# Power_Distribution.net
KiCad netlist of a schematic drawn in Altium Designer
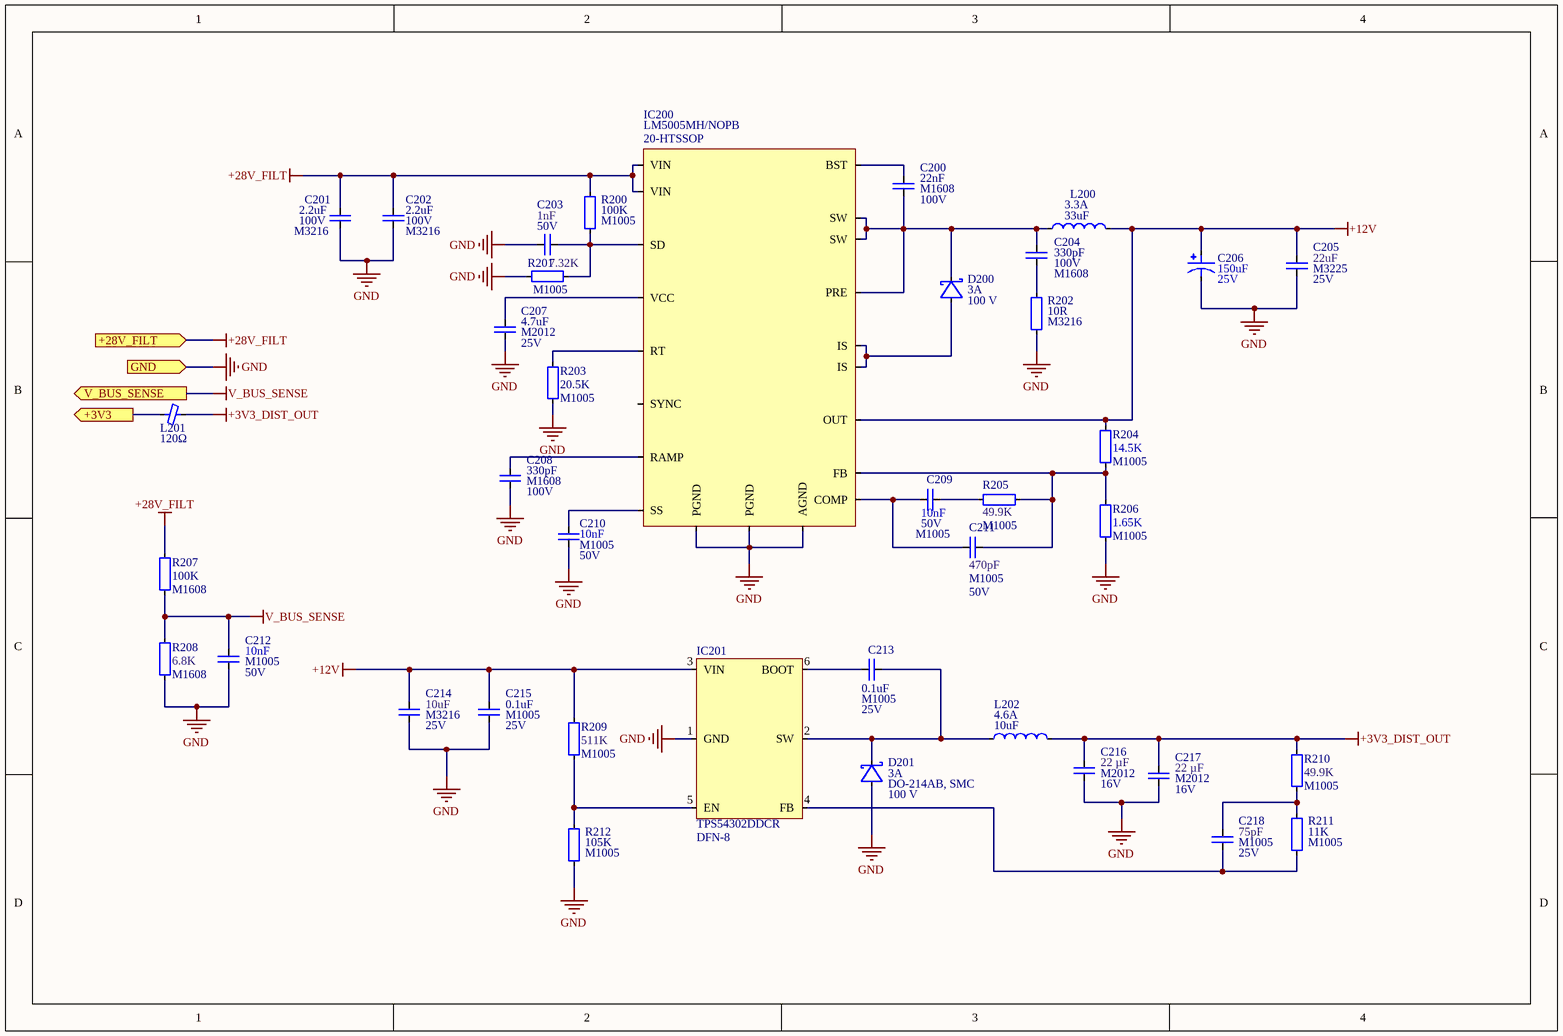
[diagram p0: Power_Distribution.SchDoc]

(export (version "E")
  (design (tool "Eeschema 10.0.6"))
  (components
    (comp (ref "C200")
      (value "22nF")
      (footprint "Capacitor_Seramic_M1608_I0603")
      (description "Cap, Cer, 22nF, 100V, M1608")
      (fields
        (field (name "TOLERANCE") "±10%")
        (field (name "MANUFACTURER PART NUMBER") "CC0603KRX7R0BB223")
        (field (name "PACKAGE") "M1608")
        (field (name "RATED VOLTAGE") "100V")
      )
      (libsource (lib "Capacitor") (part "Capacitor_Seramic"))
    )
    (comp (ref "C201")
      (value "2.2uF")
      (footprint "Capacitor_Seramic_M2012_I0805")
      (description "Cap, Cer, 2.2uF, 100V, M3216")
      (fields
        (field (name "TOLERANCE") "±10%")
        (field (name "MANUFACTURER PART NUMBER") "AC1206KKX7R0BB225")
        (field (name "PACKAGE") "M3216")
        (field (name "RATED VOLTAGE") "100V")
      )
      (libsource (lib "Capacitor") (part "Capacitor_Seramic"))
    )
    (comp (ref "C202")
      (value "2.2uF")
      (footprint "Capacitor_Seramic_M2012_I0805")
      (description "Cap, Cer, 2.2uF, 100V, M3216")
      (fields
        (field (name "TOLERANCE") "±10%")
        (field (name "MANUFACTURER PART NUMBER") "AC1206KKX7R0BB225")
        (field (name "PACKAGE") "M3216")
        (field (name "RATED VOLTAGE") "100V")
      )
      (libsource (lib "Capacitor") (part "Capacitor_Seramic"))
    )
    (comp (ref "C203")
      (value "1nF")
      (footprint "Capacitor_Seramic_M1005_I0402")
      (description "Cap, Cer, 1nF, 50V, M1005")
      (fields
        (field (name "TOLERANCE") "±10%")
        (field (name "MANUFACTURER PART NUMBER") "CC0402KRX7R9BB102")
        (field (name "RATED VOLTAGE") "50V")
        (field (name "COMPONENTLINK1URL") "C:\\Users\\User\\OneDrive - Karadeniz Teknik University\\Masaüstü\\pcb\\Altium-Designer-ile-Elektronik-Devre-Karti-Tasarimi_2024-main\\Datasheets\\Capacitor\\Walsin - Multilayer Ceramic Capacitors.pdf")
      )
      (libsource (lib "Capacitor") (part "Capacitor_Seramic"))
    )
    (comp (ref "C204")
      (value "330pF")
      (footprint "Capacitor_Seramic_M1608_I0603")
      (description "Cap, Cer, 330pF, 100V, M1608")
      (fields
        (field (name "TOLERANCE") "±5%")
        (field (name "MANUFACTURER PART NUMBER") "CC0603JRNPO0BN331")
        (field (name "PACKAGE") "M1608")
        (field (name "RATED VOLTAGE") "100V")
      )
      (libsource (lib "Capacitor") (part "Capacitor_Seramic"))
    )
    (comp (ref "C205")
      (value "22uF")
      (footprint "Capacitor_Seramic_M3225_I1210")
      (description "Cap, Cer, 22uF, 25V, M3225")
      (fields
        (field (name "TOLERANCE") "±10%")
        (field (name "MANUFACTURER PART NUMBER") "GRM32ER71E226KE15L")
        (field (name "PACKAGE") "M3225")
        (field (name "RATED VOLTAGE") "25V")
        (field (name "COMPONENTLINK1URL") "C:\\Users\\User\\OneDrive - Karadeniz Teknik University\\Masaüstü\\pcb\\Altium-Designer-ile-Elektronik-Devre-Karti-Tasarimi_2024-main\\Datasheets\\Capacitor\\Murata - Multilayer Ceramic Capacitors.pdf")
      )
      (libsource (lib "Capacitor") (part "Capacitor_Seramic"))
    )
    (comp (ref "C206")
      (value "150uF")
      (footprint "CAP_ZK_D8_PAN")
      (description "Cap, Aluminum")
      (fields
        (field (name "TOLERANCE") "±20%")
        (field (name "MANUFACTURER") "Panasonic")
        (field (name "RATED VOLTAGE") "25V")
      )
      (libsource (lib "Capacitor") (part "Capacitor_Aluminum"))
    )
    (comp (ref "C207")
      (value "4.7uF")
      (footprint "Capacitor_Seramic_M2012_I0805")
      (description "Cap, Cer, 4.7uF, 25V, M2012")
      (fields
        (field (name "TOLERANCE") "±10%")
        (field (name "MANUFACTURER PART NUMBER") "C2012X7R1E475K125AB")
        (field (name "PACKAGE") "M2012")
        (field (name "RATED VOLTAGE") "25V")
      )
      (libsource (lib "Capacitor") (part "Capacitor_Seramic"))
    )
    (comp (ref "C208")
      (value "330pF")
      (footprint "Capacitor_Seramic_M1608_I0603")
      (description "Cap, Cer, 330pF, 100V, M1608")
      (fields
        (field (name "TOLERANCE") "±5%")
        (field (name "MANUFACTURER PART NUMBER") "CC0603JRNPO0BN331")
        (field (name "PACKAGE") "M1608")
        (field (name "RATED VOLTAGE") "100V")
      )
      (libsource (lib "Capacitor") (part "Capacitor_Seramic"))
    )
    (comp (ref "C209")
      (value "10nF")
      (footprint "Capacitor_Seramic_M1005_I0402")
      (description "Cap, Cer, 10nF, 50V, M1005")
      (fields
        (field (name "TOLERANCE") "±10%")
        (field (name "MANUFACTURER PART NUMBER") "CC0402KRX7R9BB103")
        (field (name "PACKAGE") "M1005")
        (field (name "RATED VOLTAGE") "50V")
      )
      (libsource (lib "Capacitor") (part "Capacitor_Seramic"))
    )
    (comp (ref "C210")
      (value "10nF")
      (footprint "Capacitor_Seramic_M1005_I0402")
      (description "Cap, Cer, 10nF, 50V, M1005")
      (fields
        (field (name "TOLERANCE") "±10%")
        (field (name "MANUFACTURER PART NUMBER") "CC0402KRX7R9BB103")
        (field (name "PACKAGE") "M1005")
        (field (name "RATED VOLTAGE") "50V")
      )
      (libsource (lib "Capacitor") (part "Capacitor_Seramic"))
    )
    (comp (ref "C211")
      (value "470pF")
      (footprint "Capacitor_Seramic_M1005_I0402")
      (description "Cap, Cer, 470pF, 50V, M1005")
      (fields
        (field (name "TOLERANCE") "±5%")
        (field (name "MANUFACTURER PART NUMBER") "CC0402JRNPO9BN471")
        (field (name "PACKAGE") "M1005")
        (field (name "RATED VOLTAGE") "50V")
        (field (name "COMPONENTLINK1URL") "C:\\Users\\User\\OneDrive - Karadeniz Teknik University\\Masaüstü\\pcb\\Altium-Designer-ile-Elektronik-Devre-Karti-Tasarimi_2024-main\\Datasheets\\Capacitor\\Walsin - Multilayer Ceramic Capacitors.pdf")
      )
      (libsource (lib "Capacitor") (part "Capacitor_Seramic"))
    )
    (comp (ref "C212")
      (value "10nF")
      (footprint "Capacitor_Seramic_M1005_I0402")
      (description "Cap, Cer, 10nF, 50V, M1005")
      (fields
        (field (name "TOLERANCE") "±10%")
        (field (name "MANUFACTURER PART NUMBER") "CC0402KRX7R9BB103")
        (field (name "PACKAGE") "M1005")
        (field (name "RATED VOLTAGE") "50V")
      )
      (libsource (lib "Capacitor") (part "Capacitor_Seramic"))
    )
    (comp (ref "C213")
      (value "0.1uF")
      (footprint "Capacitor_Seramic_M1005_I0402")
      (description "Cap, Cer, 0.1uF, 25V, M1005")
      (fields
        (field (name "TOLERANCE") "±10%")
        (field (name "MANUFACTURER PART NUMBER") "CC0402KRX7R8BB104")
        (field (name "PACKAGE") "M1005")
        (field (name "RATED VOLTAGE") "25V")
      )
      (libsource (lib "Capacitor") (part "Capacitor_Seramic"))
    )
    (comp (ref "C214")
      (value "10uF")
      (footprint "Capacitor_Seramic_M3216_I1206")
      (description "Cap, Cer, 10uF, 25V, M3216")
      (fields
        (field (name "TOLERANCE") "±10%")
        (field (name "MANUFACTURER PART NUMBER") "CL31B106KAHNFNE")
        (field (name "PACKAGE") "M3216")
        (field (name "RATED VOLTAGE") "25V")
        (field (name "COMPONENTLINK1URL") "C:\\Users\\User\\OneDrive - Karadeniz Teknik University\\Masaüstü\\pcb\\Altium-Designer-ile-Elektronik-Devre-Karti-Tasarimi_2024-main\\Datasheets\\Capacitor\\Walsin - Multilayer Ceramic Capacitors.pdf")
      )
      (libsource (lib "Capacitor") (part "Capacitor_Seramic"))
    )
    (comp (ref "C215")
      (value "0.1uF")
      (footprint "Capacitor_Seramic_M1005_I0402")
      (description "Cap, Cer, 0.1uF, 25V, M1005")
      (fields
        (field (name "TOLERANCE") "±10%")
        (field (name "MANUFACTURER PART NUMBER") "CC0402KRX7R8BB104")
        (field (name "PACKAGE") "M1005")
        (field (name "RATED VOLTAGE") "25V")
      )
      (libsource (lib "Capacitor") (part "Capacitor_Seramic"))
    )
    (comp (ref "C216")
      (value "22 µF")
      (footprint "Capacitor_Seramic_M2012_I0805")
      (description "Cap, Cer, 22uF, 16V, M2012")
      (fields
        (field (name "TOLERANCE") "20%")
        (field (name "MANUFACTURER PART NUMBER") "GRM21BR61C226ME44L")
        (field (name "PACKAGE") "M2012")
        (field (name "RATED VOLTAGE") "16V")
        (field (name "COMPONENTLINK1URL") "C:\\Users\\User\\OneDrive - Karadeniz Teknik University\\Masaüstü\\pcb\\Altium-Designer-ile-Elektronik-Devre-Karti-Tasarimi_2024-main\\Datasheets\\Capacitor\\Murata - Multilayer Ceramic Capacitors.pdf")
      )
      (libsource (lib "Capacitor") (part "Capacitor_Seramic"))
    )
    (comp (ref "C217")
      (value "22 µF")
      (footprint "Capacitor_Seramic_M2012_I0805")
      (description "Cap, Cer, 22uF, 16V, M2012")
      (fields
        (field (name "TOLERANCE") "20%")
        (field (name "MANUFACTURER PART NUMBER") "GRM21BR61C226ME44L")
        (field (name "PACKAGE") "M2012")
        (field (name "RATED VOLTAGE") "16V")
        (field (name "COMPONENTLINK1URL") "C:\\Users\\User\\OneDrive - Karadeniz Teknik University\\Masaüstü\\pcb\\Altium-Designer-ile-Elektronik-Devre-Karti-Tasarimi_2024-main\\Datasheets\\Capacitor\\Murata - Multilayer Ceramic Capacitors.pdf")
      )
      (libsource (lib "Capacitor") (part "Capacitor_Seramic"))
    )
    (comp (ref "C218")
      (value "75pF")
      (footprint "Capacitor_Seramic_M1005_I0402")
      (description "Cap, Cer, 75pF, 25V, M1005")
      (fields
        (field (name "TOLERANCE") "±5%")
        (field (name "MANUFACTURER PART NUMBER") "CC0402JRNPO9BN750")
        (field (name "PACKAGE") "M1005")
        (field (name "RATED VOLTAGE") "25V")
        (field (name "COMPONENTLINK1URL") "C:\\Users\\User\\OneDrive - Karadeniz Teknik University\\Masaüstü\\pcb\\Altium-Designer-ile-Elektronik-Devre-Karti-Tasarimi_2024-main\\Datasheets\\Capacitor\\Walsin - Multilayer Ceramic Capacitors.pdf")
      )
      (libsource (lib "Capacitor") (part "Capacitor_Seramic"))
    )
    (comp (ref "D200")
      (value "Diode_Schottky")
      (footprint "SMC_DIO")
      (fields
        (field (name "MANUFACTURER PART NUMBER") "B3100-13-F")
        (field (name "MANUFACTURER") "Diodes Incorporated")
        (field (name "CURRENT") "3A")
        (field (name "VOLTAGE") "100 V")
      )
      (libsource (lib "Diode") (part "Diode_Schottky"))
    )
    (comp (ref "D201")
      (value "Diode_Schottky")
      (footprint "SMC_DIO")
      (fields
        (field (name "MANUFACTURER PART NUMBER") "B3100-13-F")
        (field (name "MANUFACTURER") "Diodes Incorporated")
        (field (name "CURRENT") "3A")
        (field (name "PACKAGE") "DO-214AB, SMC")
        (field (name "VOLTAGE") "100 V")
      )
      (libsource (lib "Diode") (part "Diode_Schottky"))
    )
    (comp (ref "IC200")
      (value "TI, LM5005, 20-HTSSOP")
      (footprint "TI, LM5005, 20-HTSSOP")
      (description "IC, Power, DC-DC, Texas Instruments, LM5005, HTSSOP, 20 Pin")
      (fields
        (field (name "MANUFACTURER") "Texas Instruments")
        (field (name "MANUFACTURER PART NUMBER") "LM5005MH/NOPB")
        (field (name "PACKAGE") "20-HTSSOP")
        (field (name "COMPONENTLINK1URL") "C:\\Users\\User\\OneDrive - Karadeniz Teknik University\\Masaüstü\\pcb\\kütüphane\\Datasheet\\lm5005.pdf")
      )
      (libsource (lib "IC - Power - DC-DC") (part "TI, LM5005, 20-HTSSOP"))
    )
    (comp (ref "IC201")
      (value "TI, TPS54302")
      (footprint "SOT-23-6Pin")
      (description "IC, Power, DC-DC, Texas Instruments, TPS54302")
      (fields
        (field (name "MANUFACTURER") "Texas Instruments")
        (field (name "MANUFACTURER PART NUMBER") "TPS54302DDCR")
        (field (name "PACKAGE") "DFN-8")
        (field (name "COMPONENTLINK1URL") "C:\\Users\\User\\OneDrive - Karadeniz Teknik University\\Masaüstü\\pcb\\kütüphane\\Datasheet\\tps54302.pdf")
      )
      (libsource (lib "IC - Power - DC-DC") (part "TI, TPS54302"))
    )
    (comp (ref "L200")
      (value "33uF")
      (footprint "Bourns - SRR1280")
      (description "Inductor")
      (fields
        (field (name "MANUFACTURER PART NUMBER") "SRR1280-330M")
        (field (name "MANUFACTURER") "Bourns Inc.")
        (field (name "SATURATION CURRENT") "3.3A")
      )
      (libsource (lib "Inductor") (part "Inductor"))
    )
    (comp (ref "L201")
      (value "120Ω")
      (footprint "Ferrite_Bead_Smd_M1608_I0603")
      (fields
        (field (name "MANUFACTURER PART NUMBER") "BLM18PG121SN1D")
        (field (name "MANUFACTURER") "Murata Electronics")
        (field (name "Comment") "Ferrite Bead")
      )
      (libsource (lib "Inductor") (part "Ferrite Bead"))
    )
    (comp (ref "L202")
      (value "10uF")
      (footprint "Bourns - SRN6045TA")
      (description "Inductor")
      (fields
        (field (name "MANUFACTURER PART NUMBER") "SRN6045TA-100MCT-ND")
        (field (name "MANUFACTURER") "Bourns Inc.")
        (field (name "SATURATION CURRENT") "4.6A")
      )
      (libsource (lib "Inductor") (part "Inductor"))
    )
    (comp (ref "R200")
      (value "100K")
      (footprint "Resistor_SMD_M1005_I0402")
      (description "Res, 100K, 1%, M1005")
      (fields
        (field (name "MANUFACTURER") "Yageo")
        (field (name "MANUFACTURER PART NUMBER") "RC0402FR-07100KP")
        (field (name "PACKAGE") "M1005")
      )
      (libsource (lib "Resistor") (part "Resistor"))
    )
    (comp (ref "R201")
      (value "7.32K")
      (footprint "Resistor_SMD_M1005_I0402")
      (description "Res, 7.32K, 1%, M1005")
      (fields
        (field (name "MANUFACTURER") "YAGEO")
        (field (name "MANUFACTURER PART NUMBER") "RC0402FR-077K32L")
        (field (name "PACKAGE") "M1005")
      )
      (libsource (lib "Resistor") (part "Resistor"))
    )
    (comp (ref "R202")
      (value "10R")
      (footprint "Resistor_SMD_M3216_I1206")
      (fields
        (field (name "MANUFACTURER") "Yageo")
        (field (name "MANUFACTURER PART NUMBER") "RC1206FR-0710RL")
        (field (name "PACKAGE") "M3216")
        (field (name "Comment") "Resistor")
      )
      (libsource (lib "Resistor") (part "Resistor"))
    )
    (comp (ref "R203")
      (value "20.5K")
      (footprint "Resistor_SMD_M1005_I0402")
      (description "Res, 20.5K, 1%, M1005")
      (fields
        (field (name "MANUFACTURER") "YAGEO")
        (field (name "MANUFACTURER PART NUMBER") "RC0402FR-0720K5L")
        (field (name "PACKAGE") "M1005")
      )
      (libsource (lib "Resistor") (part "Resistor"))
    )
    (comp (ref "R204")
      (value "14.5K")
      (footprint "Resistor_SMD_M1005_I0402")
      (description "Res, 1.5K, 1%, M1005")
      (fields
        (field (name "MANUFACTURER") "Yageo")
        (field (name "MANUFACTURER PART NUMBER") "RC0402FR-071K5L")
        (field (name "PACKAGE") "M1005")
      )
      (libsource (lib "Resistor") (part "Resistor"))
    )
    (comp (ref "R205")
      (value "49.9K")
      (footprint "Resistor_SMD_M1005_I0402")
      (description "Res, 49.9K, 1%, M1005")
      (fields
        (field (name "MANUFACTURER") "YAGEO")
        (field (name "MANUFACTURER PART NUMBER") "RC0402FR-0749K9L")
        (field (name "PACKAGE") "M1005")
      )
      (libsource (lib "Resistor") (part "Resistor"))
    )
    (comp (ref "R206")
      (value "1.65K")
      (footprint "Resistor_SMD_M1005_I0402")
      (description "Res, 1.65K, 1%, M1005")
      (fields
        (field (name "MANUFACTURER") "YAGEO")
        (field (name "MANUFACTURER PART NUMBER") "RC0402FR-071K65L")
        (field (name "PACKAGE") "M1005")
      )
      (libsource (lib "Resistor") (part "Resistor"))
    )
    (comp (ref "R207")
      (value "100K")
      (footprint "Resistor_SMD_M1608_I0603")
      (description "Res, 100K, 1%, M1608")
      (fields
        (field (name "MANUFACTURER") "YAGEO")
        (field (name "MANUFACTURER PART NUMBER") "RC0603FR-07100KL")
        (field (name "PACKAGE") "M1608")
      )
      (libsource (lib "Resistor") (part "Resistor"))
    )
    (comp (ref "R208")
      (value "6.8K")
      (footprint "Resistor_SMD_M1608_I0603")
      (description "Res, 6.8K, 1%, M1608")
      (fields
        (field (name "MANUFACTURER") "YAGEO")
        (field (name "MANUFACTURER PART NUMBER") "RC0603FR-076K8L")
        (field (name "PACKAGE") "M1608")
      )
      (libsource (lib "Resistor") (part "Resistor"))
    )
    (comp (ref "R209")
      (value "511K")
      (footprint "Resistor_SMD_M1005_I0402")
      (description "Res, 511K, 1%, M1005")
      (fields
        (field (name "MANUFACTURER") "YAGEO")
        (field (name "MANUFACTURER PART NUMBER") "RC0402FR-07511KL")
        (field (name "PACKAGE") "M1005")
      )
      (libsource (lib "Resistor") (part "Resistor"))
    )
    (comp (ref "R210")
      (value "49.9K")
      (footprint "Resistor_SMD_M1005_I0402")
      (description "Res, 49.9K, 1%, M1005")
      (fields
        (field (name "MANUFACTURER") "YAGEO")
        (field (name "MANUFACTURER PART NUMBER") "RC0402FR-0749K9L")
        (field (name "PACKAGE") "M1005")
      )
      (libsource (lib "Resistor") (part "Resistor"))
    )
    (comp (ref "R211")
      (value "11K")
      (footprint "Resistor_SMD_M1005_I0402")
      (description "Res, 11K, 1%, M1005")
      (fields
        (field (name "MANUFACTURER") "YAGEO")
        (field (name "MANUFACTURER PART NUMBER") "RC0402FR-0711KL")
        (field (name "PACKAGE") "M1005")
      )
      (libsource (lib "Resistor") (part "Resistor"))
    )
    (comp (ref "R212")
      (value "105K")
      (footprint "Resistor_SMD_M1005_I0402")
      (description "Res, 105K, 1%, M1005")
      (fields
        (field (name "MANUFACTURER") "YAGEO")
        (field (name "MANUFACTURER PART NUMBER") "RC0402FR-07105KL")
        (field (name "PACKAGE") "M1005")
      )
      (libsource (lib "Resistor") (part "Resistor"))
    )
  )
  (nets
    (net (code "1") (name "+3V3_DIST_OUT") (class "Default")
      (node (ref "C216") (pin "1") (pinfunction "1_1") (pintype "passive"))
      (node (ref "C217") (pin "1") (pinfunction "1_1") (pintype "passive"))
      (node (ref "L201") (pin "2") (pinfunction "2_2") (pintype "passive"))
      (node (ref "L202") (pin "2") (pinfunction "2_2") (pintype "passive"))
      (node (ref "R210") (pin "1") (pinfunction "1_1") (pintype "passive"))
    )
    (net (code "2") (name "+12V") (class "Default")
      (node (ref "C205") (pin "1") (pinfunction "1_1") (pintype "passive"))
      (node (ref "C206") (pin "1") (pinfunction "1_1") (pintype "passive"))
      (node (ref "C214") (pin "1") (pinfunction "1_1") (pintype "passive"))
      (node (ref "C215") (pin "1") (pinfunction "1_1") (pintype "passive"))
      (node (ref "IC200") (pin "12-OUT") (pinfunction "OUT_12-OUT") (pintype "passive"))
      (node (ref "IC201") (pin "3") (pinfunction "VIN_3") (pintype "passive"))
      (node (ref "L200") (pin "2") (pinfunction "2_2") (pintype "passive"))
      (node (ref "R204") (pin "2") (pinfunction "2_2") (pintype "passive"))
      (node (ref "R209") (pin "1") (pinfunction "1_1") (pintype "passive"))
    )
    (net (code "3") (name "+28V_FILT") (class "Default")
      (node (ref "C201") (pin "1") (pinfunction "1_1") (pintype "passive"))
      (node (ref "C202") (pin "1") (pinfunction "1_1") (pintype "passive"))
      (node (ref "IC200") (pin "3-VIN") (pinfunction "VIN_3-VIN") (pintype "passive"))
      (node (ref "IC200") (pin "4-VIN") (pinfunction "VIN_4-VIN") (pintype "passive"))
      (node (ref "R200") (pin "1") (pinfunction "1_1") (pintype "passive"))
      (node (ref "R207") (pin "2") (pinfunction "2_2") (pintype "passive"))
    )
    (net (code "4") (name "/+3V3") (class "Default")
      (node (ref "L201") (pin "1") (pinfunction "1_1") (pintype "passive"))
    )
    (net (code "5") (name "GND") (class "Default")
      (node (ref "C201") (pin "2") (pinfunction "2_2") (pintype "passive"))
      (node (ref "C202") (pin "2") (pinfunction "2_2") (pintype "passive"))
      (node (ref "C203") (pin "2") (pinfunction "2_2") (pintype "passive"))
      (node (ref "C205") (pin "2") (pinfunction "2_2") (pintype "passive"))
      (node (ref "C206") (pin "2") (pinfunction "2_2") (pintype "passive"))
      (node (ref "C207") (pin "2") (pinfunction "2_2") (pintype "passive"))
      (node (ref "C208") (pin "2") (pinfunction "2_2") (pintype "passive"))
      (node (ref "C210") (pin "2") (pinfunction "2_2") (pintype "passive"))
      (node (ref "C212") (pin "2") (pinfunction "2_2") (pintype "passive"))
      (node (ref "C214") (pin "2") (pinfunction "2_2") (pintype "passive"))
      (node (ref "C215") (pin "2") (pinfunction "2_2") (pintype "passive"))
      (node (ref "C216") (pin "2") (pinfunction "2_2") (pintype "passive"))
      (node (ref "C217") (pin "2") (pinfunction "2_2") (pintype "passive"))
      (node (ref "D201") (pin "A") (pinfunction "Anode_A") (pintype "passive"))
      (node (ref "IC200") (pin "10-AGND") (pinfunction "AGND_10-AGND") (pintype "passive"))
      (node (ref "IC200") (pin "13-PGND") (pinfunction "PGND_13-PGND") (pintype "passive"))
      (node (ref "IC200") (pin "14-PGND") (pinfunction "PGND_14-PGND") (pintype "passive"))
      (node (ref "IC201") (pin "1") (pinfunction "GND_1") (pintype "passive"))
      (node (ref "R201") (pin "1") (pinfunction "1_1") (pintype "passive"))
      (node (ref "R202") (pin "2") (pinfunction "2_2") (pintype "passive"))
      (node (ref "R203") (pin "2") (pinfunction "2_2") (pintype "passive"))
      (node (ref "R206") (pin "1") (pinfunction "1_1") (pintype "passive"))
      (node (ref "R208") (pin "2") (pinfunction "2_2") (pintype "passive"))
      (node (ref "R212") (pin "2") (pinfunction "2_2") (pintype "passive"))
    )
    (net (code "6") (name "Net-(C204-Pad2)") (class "Default")
      (node (ref "C204") (pin "2") (pinfunction "2_2") (pintype "passive"))
      (node (ref "R202") (pin "1") (pinfunction "1_1") (pintype "passive"))
    )
    (net (code "7") (name "Net-(C209-Pad2)") (class "Default")
      (node (ref "C209") (pin "2") (pinfunction "2_2") (pintype "passive"))
      (node (ref "R205") (pin "2") (pinfunction "2_2") (pintype "passive"))
    )
    (net (code "8") (name "Net-(C218-Pad1)") (class "Default")
      (node (ref "C218") (pin "1") (pinfunction "1_1") (pintype "passive"))
      (node (ref "R210") (pin "2") (pinfunction "2_2") (pintype "passive"))
      (node (ref "R211") (pin "1") (pinfunction "1_1") (pintype "passive"))
    )
    (net (code "9") (name "Net-(D200-Anode)") (class "Default")
      (node (ref "D200") (pin "A") (pinfunction "Anode_A") (pintype "passive"))
      (node (ref "IC200") (pin "15-IS") (pinfunction "IS_15-IS") (pintype "passive"))
      (node (ref "IC200") (pin "16-IS") (pinfunction "IS_16-IS") (pintype "passive"))
    )
    (net (code "10") (name "Net-(D200-Katode)") (class "Default")
      (node (ref "C200") (pin "2") (pinfunction "2_2") (pintype "passive"))
      (node (ref "C204") (pin "1") (pinfunction "1_1") (pintype "passive"))
      (node (ref "D200") (pin "K") (pinfunction "Katode_K") (pintype "passive"))
      (node (ref "IC200") (pin "17-SW") (pinfunction "SW_17-SW") (pintype "passive"))
      (node (ref "IC200") (pin "18-SW") (pinfunction "SW_18-SW") (pintype "passive"))
      (node (ref "IC200") (pin "19-PRE") (pinfunction "PRE_19-PRE") (pintype "passive"))
      (node (ref "L200") (pin "1") (pinfunction "1_1") (pintype "passive"))
    )
    (net (code "11") (name "Net-(D201-Katode)") (class "Default")
      (node (ref "C213") (pin "2") (pinfunction "2_2") (pintype "passive"))
      (node (ref "D201") (pin "K") (pinfunction "Katode_K") (pintype "passive"))
      (node (ref "IC201") (pin "2") (pinfunction "SW_2") (pintype "passive"))
      (node (ref "L202") (pin "1") (pinfunction "1_1") (pintype "passive"))
    )
    (net (code "12") (name "Net-(IC200-BST)") (class "Default")
      (node (ref "C200") (pin "1") (pinfunction "1_1") (pintype "passive"))
      (node (ref "IC200") (pin "20-BST") (pinfunction "BST_20-BST") (pintype "passive"))
    )
    (net (code "13") (name "Net-(IC200-COMP)") (class "Default")
      (node (ref "C209") (pin "1") (pinfunction "1_1") (pintype "passive"))
      (node (ref "C211") (pin "2") (pinfunction "2_2") (pintype "passive"))
      (node (ref "IC200") (pin "6-COMP") (pinfunction "COMP_6-COMP") (pintype "passive"))
    )
    (net (code "14") (name "Net-(IC200-FB)") (class "Default")
      (node (ref "C211") (pin "1") (pinfunction "1_1") (pintype "passive"))
      (node (ref "IC200") (pin "7-FB") (pinfunction "FB_7-FB") (pintype "passive"))
      (node (ref "R204") (pin "1") (pinfunction "1_1") (pintype "passive"))
      (node (ref "R205") (pin "1") (pinfunction "1_1") (pintype "passive"))
      (node (ref "R206") (pin "2") (pinfunction "2_2") (pintype "passive"))
    )
    (net (code "15") (name "Net-(IC200-RAMP)") (class "Default")
      (node (ref "C208") (pin "1") (pinfunction "1_1") (pintype "passive"))
      (node (ref "IC200") (pin "9-RAMP") (pinfunction "RAMP_9-RAMP") (pintype "passive"))
    )
    (net (code "16") (name "Net-(IC200-RT)") (class "Default")
      (node (ref "IC200") (pin "8-RT") (pinfunction "RT_8-RT") (pintype "passive"))
      (node (ref "R203") (pin "1") (pinfunction "1_1") (pintype "passive"))
    )
    (net (code "17") (name "Net-(IC200-SD)") (class "Default")
      (node (ref "C203") (pin "1") (pinfunction "1_1") (pintype "passive"))
      (node (ref "IC200") (pin "2-SD") (pinfunction "SD_2-SD") (pintype "passive"))
      (node (ref "R200") (pin "2") (pinfunction "2_2") (pintype "passive"))
      (node (ref "R201") (pin "2") (pinfunction "2_2") (pintype "passive"))
    )
    (net (code "18") (name "Net-(IC200-SS)") (class "Default")
      (node (ref "C210") (pin "1") (pinfunction "1_1") (pintype "passive"))
      (node (ref "IC200") (pin "11-SS") (pinfunction "SS_11-SS") (pintype "passive"))
    )
    (net (code "19") (name "Net-(IC200-VCC)") (class "Default")
      (node (ref "C207") (pin "1") (pinfunction "1_1") (pintype "passive"))
      (node (ref "IC200") (pin "1-VCC") (pinfunction "VCC_1-VCC") (pintype "passive"))
    )
    (net (code "20") (name "Net-(IC201-BOOT)") (class "Default")
      (node (ref "C213") (pin "1") (pinfunction "1_1") (pintype "passive"))
      (node (ref "IC201") (pin "6") (pinfunction "BOOT_6") (pintype "passive"))
    )
    (net (code "21") (name "Net-(IC201-EN)") (class "Default")
      (node (ref "IC201") (pin "5") (pinfunction "EN_5") (pintype "passive"))
      (node (ref "R209") (pin "2") (pinfunction "2_2") (pintype "passive"))
      (node (ref "R212") (pin "1") (pinfunction "1_1") (pintype "passive"))
    )
    (net (code "22") (name "Net-(IC201-FB)") (class "Default")
      (node (ref "C218") (pin "2") (pinfunction "2_2") (pintype "passive"))
      (node (ref "IC201") (pin "4") (pinfunction "FB_4") (pintype "passive"))
      (node (ref "R211") (pin "2") (pinfunction "2_2") (pintype "passive"))
    )
    (net (code "23") (name "V_BUS_SENSE") (class "Default")
      (node (ref "C212") (pin "1") (pinfunction "1_1") (pintype "passive"))
      (node (ref "R207") (pin "1") (pinfunction "1_1") (pintype "passive"))
      (node (ref "R208") (pin "1") (pinfunction "1_1") (pintype "passive"))
    )
    (net (code "24") (name "unconnected-(IC200-SYNC-Pad5-SYNC)") (class "Default")
      (node (ref "IC200") (pin "5-SYNC") (pinfunction "SYNC_5-SYNC") (pintype "passive"))
    )
  )
)
